# PAGE2old.net
KiCad netlist of a schematic drawn in Altium Designer
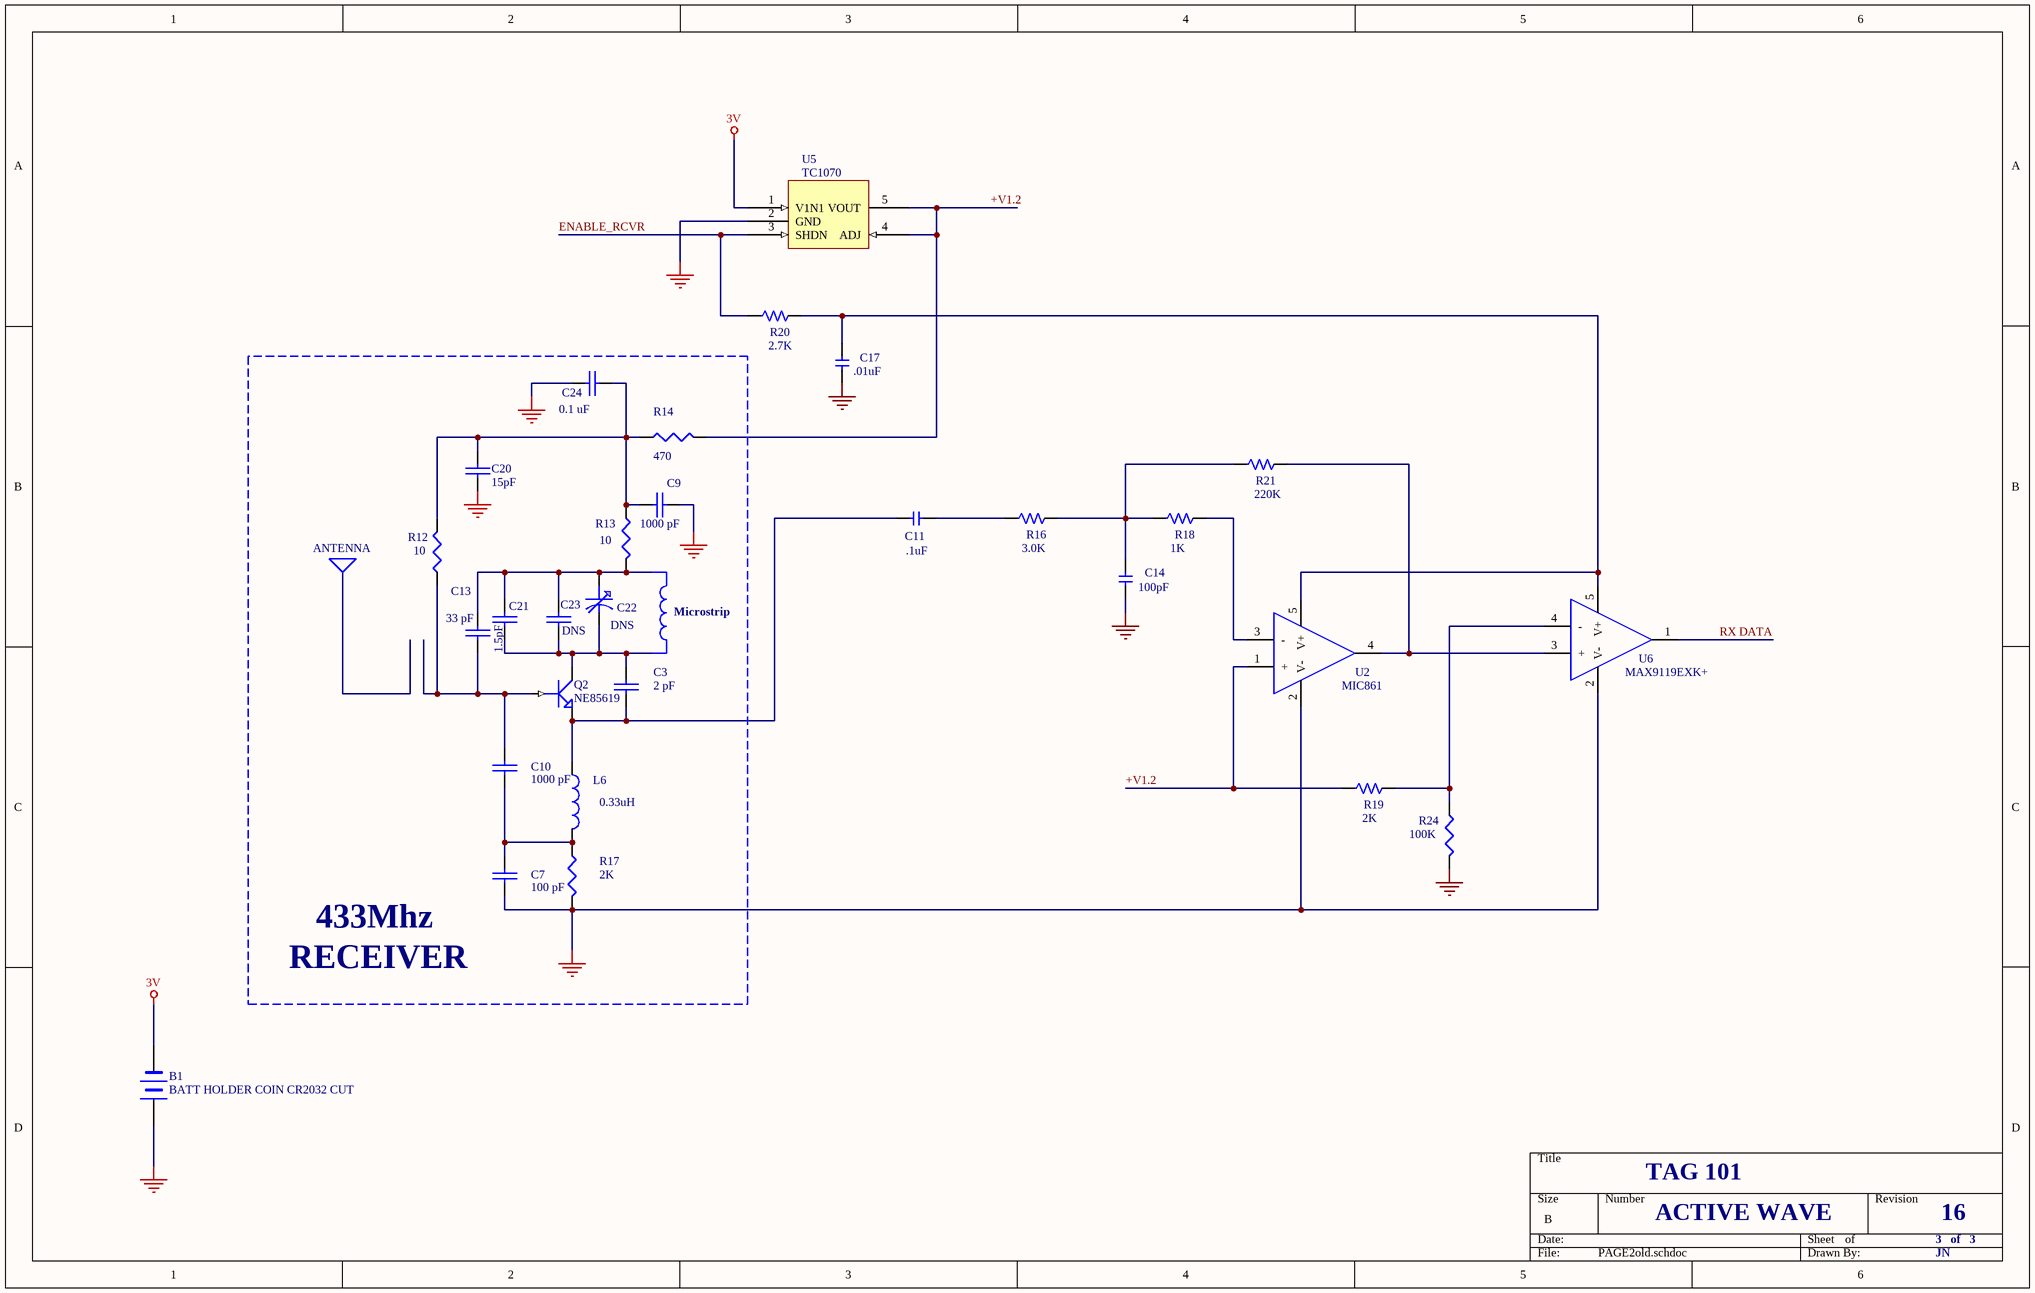
[diagram p0: PAGE2old.schdoc]

(export (version "E")
  (design (tool "Eeschema 10.0.6"))
  (components
    (comp (ref "B1")
      (value "BATT HOLDER COIN CR2032 CUT")
      (footprint "BATTERY COIN CR2032")
      (description "Battery")
      (libsource (lib "*") (part "BATTERY"))
    )
    (comp (ref "C3")
      (value "2 pF")
      (footprint "0603")
      (description "Capacitor")
      (libsource (lib "*") (part "CAP"))
    )
    (comp (ref "C7")
      (value "100 pF")
      (footprint "0603")
      (description "Capacitor")
      (libsource (lib "*") (part "CAP"))
    )
    (comp (ref "C9")
      (value "1000 pF")
      (footprint "0603")
      (description "Capacitor")
      (libsource (lib "*") (part "CAP"))
    )
    (comp (ref "C10")
      (value "1000 pF")
      (footprint "0603")
      (description "Capacitor")
      (libsource (lib "*") (part "CAP"))
    )
    (comp (ref "C11") (value ".1uF") (footprint "0603") (libsource (lib "*") (part "C")))
    (comp (ref "C13")
      (value "33 pF")
      (footprint "0603")
      (description "Capacitor")
      (libsource (lib "*") (part "CAP"))
    )
    (comp (ref "C14") (value "100pF") (footprint "0603") (libsource (lib "*") (part "C")))
    (comp (ref "C17") (value ".01uF") (footprint "0603") (libsource (lib "*") (part "C")))
    (comp (ref "C20")
      (value "15pF")
      (footprint "0603")
      (description "Capacitor")
      (libsource (lib "*") (part "CAP"))
    )
    (comp (ref "C21")
      (value "1.5pF")
      (footprint "0603")
      (description "Capacitor")
      (libsource (lib "*") (part "CAP"))
    )
    (comp (ref "C22") (value "DNS") (footprint "0603") (libsource (lib "*") (part "CAPACITOR VAR")))
    (comp (ref "C23")
      (value "DNS")
      (footprint "0603")
      (description "Capacitor")
      (libsource (lib "*") (part "CAP"))
    )
    (comp (ref "C24")
      (value "0.1 uF")
      (footprint "0603")
      (description "Capacitor")
      (libsource (lib "*") (part "CAP"))
    )
    (comp (ref "L6") (value "0.33uH") (footprint "0603") (libsource (lib "*") (part "INDUCTOR")))
    (comp (ref "Q2")
      (value "NE85619")
      (footprint "3 PIN ULTRA SUPER MINI MOLD")
      (description "NPN Transistor")
      (libsource (lib "*") (part "NPN1"))
    )
    (comp (ref "R12") (value "10") (footprint "0603") (libsource (lib "") (part "R_1")))
    (comp (ref "R13") (value "10") (footprint "0603") (libsource (lib "") (part "R_1")))
    (comp (ref "R14") (value "470") (footprint "0603") (libsource (lib "") (part "R_1")))
    (comp (ref "R16") (value "3.0K") (footprint "0603") (libsource (lib "*") (part "R")))
    (comp (ref "R17") (value "2K") (footprint "0603") (libsource (lib "*") (part "RESISTOR")))
    (comp (ref "R18") (value "1K") (footprint "0603") (libsource (lib "*") (part "R")))
    (comp (ref "R19") (value "2K") (footprint "0603") (libsource (lib "*") (part "R")))
    (comp (ref "R20") (value "2.7K") (footprint "0603") (libsource (lib "*") (part "R")))
    (comp (ref "R21") (value "220K") (footprint "0603") (libsource (lib "*") (part "R")))
    (comp (ref "R24") (value "100K") (footprint "0603") (libsource (lib "") (part "R_1")))
    (comp (ref "U2") (value "MIC861") (libsource (lib "*") (part "OPAMP MIC861")))
    (comp (ref "U5") (value "TC1070") (footprint "SOT23-5A") (libsource (lib "*") (part "TC1070-2")))
    (comp (ref "U6")
      (value "MAX9119EXK+")
      (footprint "SC70")
      (libsource (lib "*") (part "COMPARATOR MAX9117"))
    )
  )
  (nets
    (net (code "1") (name "/+V1.2") (class "Default")
      (node (ref "R14") (pin "2") (pinfunction "2_2") (pintype "passive"))
      (node (ref "R19") (pin "1") (pinfunction "1_1") (pintype "passive"))
      (node (ref "U2") (pin "1") (pinfunction "+_1") (pintype "passive"))
      (node (ref "U5") (pin "4") (pinfunction "ADJ_4") (pintype "input"))
      (node (ref "U5") (pin "5") (pinfunction "VOUT_5") (pintype "power_in"))
    )
    (net (code "2") (name "/ENABLE_RCVR") (class "Default")
      (node (ref "R20") (pin "1") (pinfunction "1_1") (pintype "passive"))
      (node (ref "U5") (pin "3") (pinfunction "SHDN_3") (pintype "input"))
    )
    (net (code "3") (name "/RX DATA") (class "Default")
      (node (ref "U6") (pin "1") (pinfunction "OUT_1") (pintype "passive"))
    )
    (net (code "4") (name "3V") (class "Default")
      (node (ref "B1") (pin "1") (pinfunction "-_1") (pintype "passive"))
      (node (ref "U5") (pin "1") (pinfunction "V1N1_1") (pintype "input"))
    )
    (net (code "5") (name "GND") (class "Default")
      (node (ref "B1") (pin "2") (pinfunction "+_2") (pintype "passive"))
      (node (ref "C14") (pin "1") (pinfunction "1_1") (pintype "passive"))
      (node (ref "C17") (pin "1") (pinfunction "1_1") (pintype "passive"))
      (node (ref "C20") (pin "1") (pinfunction "1_1") (pintype "passive"))
      (node (ref "C24") (pin "1") (pinfunction "1_1") (pintype "passive"))
      (node (ref "C7") (pin "2") (pinfunction "2_2") (pintype "passive"))
      (node (ref "C9") (pin "2") (pinfunction "2_2") (pintype "passive"))
      (node (ref "R17") (pin "2") (pinfunction "2_2") (pintype "passive"))
      (node (ref "R24") (pin "2") (pinfunction "2_2") (pintype "passive"))
      (node (ref "U2") (pin "2") (pinfunction "V-_2") (pintype "passive"))
      (node (ref "U5") (pin "2") (pinfunction "GND_2") (pintype "power_in"))
      (node (ref "U6") (pin "2") (pinfunction "V-_2") (pintype "passive"))
    )
    (net (code "6") (name "Net-(C10-Pad1)") (class "Default")
      (node (ref "C10") (pin "1") (pinfunction "1_1") (pintype "passive"))
      (node (ref "C13") (pin "1") (pinfunction "1_1") (pintype "passive"))
      (node (ref "Q2") (pin "B") (pinfunction "B_B") (pintype "input"))
      (node (ref "R12") (pin "1") (pinfunction "1_1") (pintype "passive"))
    )
    (net (code "7") (name "Net-(C10-Pad2)") (class "Default")
      (node (ref "C10") (pin "2") (pinfunction "2_2") (pintype "passive"))
      (node (ref "C7") (pin "1") (pinfunction "1_1") (pintype "passive"))
      (node (ref "L6") (pin "2") (pinfunction "2_2") (pintype "passive"))
      (node (ref "R17") (pin "1") (pinfunction "1_1") (pintype "passive"))
    )
    (net (code "8") (name "Net-(C11-Pad1)") (class "Default")
      (node (ref "C11") (pin "1") (pinfunction "1_1") (pintype "passive"))
      (node (ref "C3") (pin "2") (pinfunction "2_2") (pintype "passive"))
      (node (ref "L6") (pin "1") (pinfunction "1_1") (pintype "passive"))
      (node (ref "Q2") (pin "E") (pinfunction "E_E") (pintype "passive"))
    )
    (net (code "9") (name "Net-(C11-Pad2)") (class "Default")
      (node (ref "C11") (pin "2") (pinfunction "2_2") (pintype "passive"))
      (node (ref "R16") (pin "1") (pinfunction "1_1") (pintype "passive"))
    )
    (net (code "10") (name "Net-(C13-Pad2)") (class "Default")
      (node (ref "C13") (pin "2") (pinfunction "2_2") (pintype "passive"))
      (node (ref "C21") (pin "1") (pinfunction "1_1") (pintype "passive"))
      (node (ref "C22") (pin "1") (pinfunction "1_1") (pintype "passive"))
      (node (ref "C23") (pin "1") (pinfunction "1_1") (pintype "passive"))
      (node (ref "R13") (pin "2") (pinfunction "2_2") (pintype "passive"))
    )
    (net (code "11") (name "Net-(C14-Pad2)") (class "Default")
      (node (ref "C14") (pin "2") (pinfunction "2_2") (pintype "passive"))
      (node (ref "R16") (pin "2") (pinfunction "2_2") (pintype "passive"))
      (node (ref "R18") (pin "1") (pinfunction "1_1") (pintype "passive"))
      (node (ref "R21") (pin "1") (pinfunction "1_1") (pintype "passive"))
    )
    (net (code "12") (name "Net-(C20-Pad2)") (class "Default")
      (node (ref "C20") (pin "2") (pinfunction "2_2") (pintype "passive"))
      (node (ref "C24") (pin "2") (pinfunction "2_2") (pintype "passive"))
      (node (ref "C9") (pin "1") (pinfunction "1_1") (pintype "passive"))
      (node (ref "R12") (pin "2") (pinfunction "2_2") (pintype "passive"))
      (node (ref "R13") (pin "1") (pinfunction "1_1") (pintype "passive"))
      (node (ref "R14") (pin "1") (pinfunction "1_1") (pintype "passive"))
    )
    (net (code "13") (name "Net-(C21-Pad2)") (class "Default")
      (node (ref "C21") (pin "2") (pinfunction "2_2") (pintype "passive"))
      (node (ref "C22") (pin "2") (pinfunction "2_2") (pintype "passive"))
      (node (ref "C23") (pin "2") (pinfunction "2_2") (pintype "passive"))
      (node (ref "C3") (pin "1") (pinfunction "1_1") (pintype "passive"))
      (node (ref "Q2") (pin "C") (pinfunction "C_C") (pintype "passive"))
    )
    (net (code "14") (name "Net-(U2--)") (class "Default")
      (node (ref "R18") (pin "2") (pinfunction "2_2") (pintype "passive"))
      (node (ref "U2") (pin "3") (pinfunction "-_3") (pintype "passive"))
    )
    (net (code "15") (name "Net-(U2-OUT)") (class "Default")
      (node (ref "R21") (pin "2") (pinfunction "2_2") (pintype "passive"))
      (node (ref "U2") (pin "4") (pinfunction "OUT_4") (pintype "passive"))
      (node (ref "U6") (pin "3") (pinfunction "+_3") (pintype "passive"))
    )
    (net (code "16") (name "Net-(U2-V+)") (class "Default")
      (node (ref "C17") (pin "2") (pinfunction "2_2") (pintype "passive"))
      (node (ref "R20") (pin "2") (pinfunction "2_2") (pintype "passive"))
      (node (ref "U2") (pin "5") (pinfunction "V+_5") (pintype "passive"))
      (node (ref "U6") (pin "5") (pinfunction "V+_5") (pintype "passive"))
    )
    (net (code "17") (name "Net-(U6--)") (class "Default")
      (node (ref "R19") (pin "2") (pinfunction "2_2") (pintype "passive"))
      (node (ref "R24") (pin "1") (pinfunction "1_1") (pintype "passive"))
      (node (ref "U6") (pin "4") (pinfunction "-_4") (pintype "passive"))
    )
  )
)
